# master.net
KiCad netlist of a schematic drawn in Altium Designer
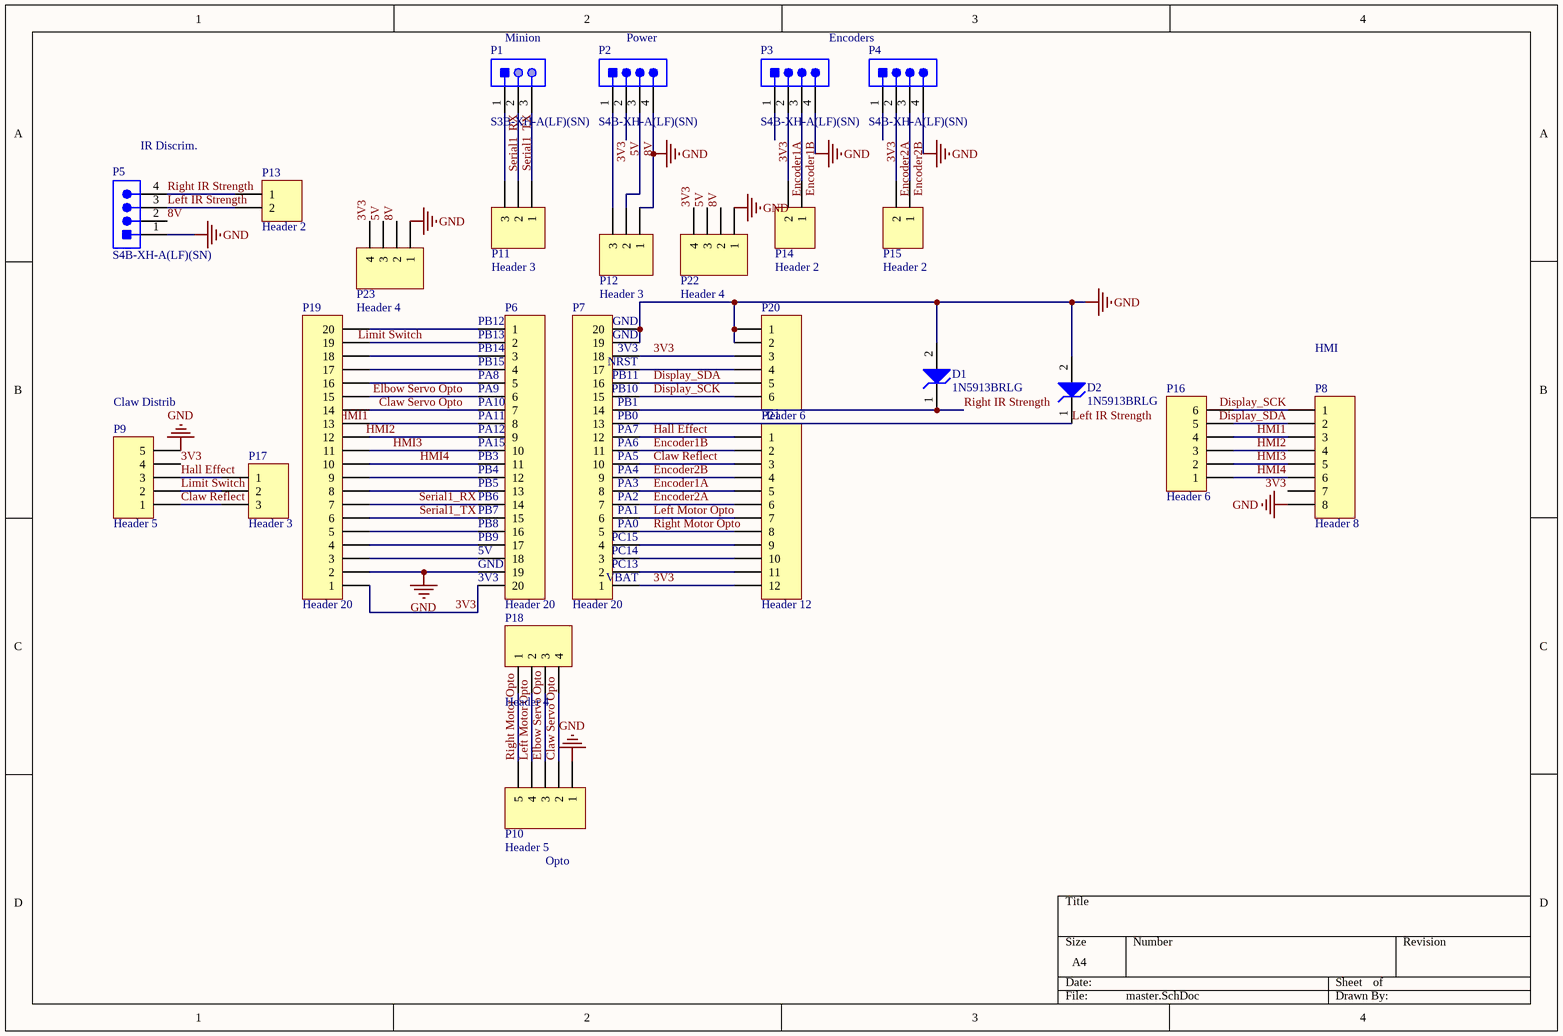
[diagram p0: master.SchDoc]

(export (version "E")
  (design (tool "Eeschema 10.0.6"))
  (components
    (comp (ref "D1")
      (value "1N5913BRLG")
      (footprint "ONSC-AXIAL_LEAD-2-59-10_P")
      (description "3 W Zener Voltage Regulator, 2-Pin Axial_Lead, Pb-Free, Tape and Reel")
      (fields (field (name "MANUFACTURER") "On Semiconductor"))
      (libsource (lib "Altium Content Vault") (part "ONSC-K1A2-2"))
    )
    (comp (ref "D2")
      (value "1N5913BRLG")
      (footprint "ONSC-AXIAL_LEAD-2-59-10_P")
      (description "3 W Zener Voltage Regulator, 2-Pin Axial_Lead, Pb-Free, Tape and Reel")
      (fields (field (name "MANUFACTURER") "On Semiconductor"))
      (libsource (lib "Altium Content Vault") (part "ONSC-K1A2-2"))
    )
    (comp (ref "P1")
      (value "S3B-XH-A(LF)(SN)")
      (footprint "JST-S3B-XH-A(LF)(SN)_V")
      (libsource (lib "Altium Content Vault") (part "CN-1P-M-R3"))
    )
    (comp (ref "P2")
      (value "S4B-XH-A(LF)(SN)")
      (footprint "JST-S4B-XH-A(LF)(SN)_V")
      (libsource (lib "") (part "CN-1P-M-R4_1"))
    )
    (comp (ref "P3")
      (value "S4B-XH-A(LF)(SN)")
      (footprint "JST-S4B-XH-A(LF)(SN)_V")
      (libsource (lib "") (part "CN-1P-M-R4_1"))
    )
    (comp (ref "P4")
      (value "S4B-XH-A(LF)(SN)")
      (footprint "JST-S4B-XH-A(LF)(SN)_V")
      (libsource (lib "") (part "CN-1P-M-R4_1"))
    )
    (comp (ref "P5")
      (value "S4B-XH-A(LF)(SN)")
      (footprint "JST-S4B-XH-A(LF)(SN)_V")
      (libsource (lib "Altium Content Vault") (part "CN-1P-M-R4"))
    )
    (comp (ref "P6")
      (value "Header 20")
      (footprint "HDR1X20")
      (description "Header, 20-Pin")
      (fields (field (name "PUBLISHER") "Altium Limited"))
      (libsource (lib "") (part "Header 20_1"))
    )
    (comp (ref "P7")
      (value "Header 20")
      (footprint "HDR1X20")
      (description "Header, 20-Pin")
      (fields (field (name "PUBLISHER") "Altium Limited"))
      (libsource (lib "Miscellaneous Connectors") (part "Header 20"))
    )
    (comp (ref "P8")
      (value "Header 8")
      (footprint "HDR1X8")
      (description "Header, 8-Pin")
      (fields (field (name "PUBLISHER") "Altium Limited"))
      (libsource (lib "Miscellaneous Connectors") (part "Header 8"))
    )
    (comp (ref "P9")
      (value "Header 5")
      (footprint "HDR1X5")
      (description "Header, 5-Pin")
      (fields (field (name "PUBLISHER") "Altium Limited"))
      (libsource (lib "Miscellaneous Connectors") (part "Header 5"))
    )
    (comp (ref "P10")
      (value "Header 5")
      (footprint "HDR1X5")
      (description "Header, 5-Pin")
      (fields (field (name "PUBLISHER") "Altium Limited"))
      (libsource (lib "") (part "Header 5_1"))
    )
    (comp (ref "P11")
      (value "Header 3")
      (footprint "HDR1X3")
      (description "Header, 3-Pin")
      (fields (field (name "PUBLISHER") "Altium Limited"))
      (libsource (lib "Miscellaneous Connectors") (part "Header 3"))
    )
    (comp (ref "P12")
      (value "Header 3")
      (footprint "HDR1X3")
      (description "Header, 3-Pin")
      (fields (field (name "PUBLISHER") "Altium Limited"))
      (libsource (lib "Miscellaneous Connectors") (part "Header 3"))
    )
    (comp (ref "P13")
      (value "Header 2")
      (footprint "HDR1X2")
      (description "Header, 2-Pin")
      (fields (field (name "PUBLISHER") "Altium Limited"))
      (libsource (lib "") (part "Header 2_1"))
    )
    (comp (ref "P14")
      (value "Header 2")
      (footprint "HDR1X2")
      (description "Header, 2-Pin")
      (fields (field (name "PUBLISHER") "Altium Limited"))
      (libsource (lib "Miscellaneous Connectors") (part "Header 2"))
    )
    (comp (ref "P15")
      (value "Header 2")
      (footprint "HDR1X2")
      (description "Header, 2-Pin")
      (fields (field (name "PUBLISHER") "Altium Limited"))
      (libsource (lib "Miscellaneous Connectors") (part "Header 2"))
    )
    (comp (ref "P16")
      (value "Header 6")
      (footprint "HDR1X6")
      (description "Header, 6-Pin")
      (fields (field (name "PUBLISHER") "Altium Limited"))
      (libsource (lib "") (part "Header 6_1"))
    )
    (comp (ref "P17")
      (value "Header 3")
      (footprint "HDR1X3")
      (description "Header, 3-Pin")
      (fields (field (name "PUBLISHER") "Altium Limited"))
      (libsource (lib "") (part "Header 3_1"))
    )
    (comp (ref "P18")
      (value "Header 4")
      (footprint "HDR1X4")
      (description "Header, 4-Pin")
      (fields (field (name "PUBLISHER") "Altium Limited"))
      (libsource (lib "Miscellaneous Connectors") (part "Header 4"))
    )
    (comp (ref "P19")
      (value "Header 20")
      (footprint "HDR1X20")
      (description "Header, 20-Pin")
      (fields (field (name "PUBLISHER") "Altium Limited"))
      (libsource (lib "Miscellaneous Connectors") (part "Header 20"))
    )
    (comp (ref "P20")
      (value "Header 6")
      (footprint "HDR1X6")
      (description "Header, 6-Pin")
      (fields (field (name "PUBLISHER") "Altium Limited"))
      (libsource (lib "Miscellaneous Connectors") (part "Header 6"))
    )
    (comp (ref "P21")
      (value "Header 12")
      (footprint "HDR1X12")
      (description "Header, 12-Pin")
      (fields (field (name "PUBLISHER") "Altium Limited"))
      (libsource (lib "Miscellaneous Connectors") (part "Header 12"))
    )
    (comp (ref "P22")
      (value "Header 4")
      (footprint "HDR1X4")
      (description "Header, 4-Pin")
      (fields (field (name "PUBLISHER") "Altium Limited"))
      (libsource (lib "") (part "Header 4_1"))
    )
    (comp (ref "P23")
      (value "Header 4")
      (footprint "HDR1X4")
      (description "Header, 4-Pin")
      (fields (field (name "PUBLISHER") "Altium Limited"))
      (libsource (lib "") (part "Header 4_1"))
    )
  )
  (nets
    (net (code "1") (name "/3V3") (class "Default")
      (node (ref "P12") (pin "3") (pinfunction "3_3") (pintype "passive"))
      (node (ref "P19") (pin "1") (pinfunction "1_1") (pintype "passive"))
      (node (ref "P2") (pin "1") (pinfunction "1_1") (pintype "passive"))
      (node (ref "P20") (pin "3") (pinfunction "3_3") (pintype "passive"))
      (node (ref "P21") (pin "12") (pinfunction "12_12") (pintype "passive"))
      (node (ref "P22") (pin "4") (pinfunction "4_4") (pintype "passive"))
      (node (ref "P23") (pin "4") (pinfunction "4_4") (pintype "passive"))
      (node (ref "P3") (pin "1") (pinfunction "1_1") (pintype "passive"))
      (node (ref "P4") (pin "1") (pinfunction "1_1") (pintype "passive"))
      (node (ref "P6") (pin "20") (pinfunction "20_20") (pintype "passive"))
      (node (ref "P7") (pin "1") (pinfunction "1_1") (pintype "passive"))
      (node (ref "P7") (pin "18") (pinfunction "18_18") (pintype "passive"))
      (node (ref "P8") (pin "7") (pinfunction "7_7") (pintype "passive"))
      (node (ref "P9") (pin "4") (pinfunction "4_4") (pintype "passive"))
    )
    (net (code "2") (name "/5V") (class "Default")
      (node (ref "P2") (pin "2") (pinfunction "2_2") (pintype "passive"))
      (node (ref "P22") (pin "3") (pinfunction "3_3") (pintype "passive"))
      (node (ref "P23") (pin "3") (pinfunction "3_3") (pintype "passive"))
    )
    (net (code "3") (name "/8V") (class "Default")
      (node (ref "P12") (pin "2") (pinfunction "2_2") (pintype "passive"))
      (node (ref "P2") (pin "3") (pinfunction "3_3") (pintype "passive"))
      (node (ref "P22") (pin "2") (pinfunction "2_2") (pintype "passive"))
      (node (ref "P23") (pin "2") (pinfunction "2_2") (pintype "passive"))
      (node (ref "P5") (pin "2") (pinfunction "2_2") (pintype "passive"))
    )
    (net (code "4") (name "/Claw Reflect") (class "Default")
      (node (ref "P17") (pin "3") (pinfunction "3_3") (pintype "passive"))
      (node (ref "P21") (pin "3") (pinfunction "3_3") (pintype "passive"))
      (node (ref "P7") (pin "10") (pinfunction "10_10") (pintype "passive"))
      (node (ref "P9") (pin "1") (pinfunction "1_1") (pintype "passive"))
    )
    (net (code "5") (name "/Claw Servo Opto") (class "Default")
      (node (ref "P10") (pin "2") (pinfunction "2_2") (pintype "passive"))
      (node (ref "P18") (pin "4") (pinfunction "4_4") (pintype "passive"))
      (node (ref "P19") (pin "14") (pinfunction "14_14") (pintype "passive"))
      (node (ref "P6") (pin "7") (pinfunction "7_7") (pintype "passive"))
    )
    (net (code "6") (name "/Display_SCK") (class "Default")
      (node (ref "P16") (pin "6") (pinfunction "6_6") (pintype "passive"))
      (node (ref "P20") (pin "6") (pinfunction "6_6") (pintype "passive"))
      (node (ref "P7") (pin "15") (pinfunction "15_15") (pintype "passive"))
      (node (ref "P8") (pin "1") (pinfunction "1_1") (pintype "passive"))
    )
    (net (code "7") (name "/Display_SDA") (class "Default")
      (node (ref "P16") (pin "5") (pinfunction "5_5") (pintype "passive"))
      (node (ref "P20") (pin "5") (pinfunction "5_5") (pintype "passive"))
      (node (ref "P7") (pin "16") (pinfunction "16_16") (pintype "passive"))
      (node (ref "P8") (pin "2") (pinfunction "2_2") (pintype "passive"))
    )
    (net (code "8") (name "/Elbow Servo Opto") (class "Default")
      (node (ref "P10") (pin "3") (pinfunction "3_3") (pintype "passive"))
      (node (ref "P18") (pin "3") (pinfunction "3_3") (pintype "passive"))
      (node (ref "P19") (pin "15") (pinfunction "15_15") (pintype "passive"))
      (node (ref "P6") (pin "6") (pinfunction "6_6") (pintype "passive"))
    )
    (net (code "9") (name "/Encoder1A") (class "Default")
      (node (ref "P14") (pin "2") (pinfunction "2_2") (pintype "passive"))
      (node (ref "P21") (pin "5") (pinfunction "5_5") (pintype "passive"))
      (node (ref "P3") (pin "2") (pinfunction "2_2") (pintype "passive"))
      (node (ref "P7") (pin "8") (pinfunction "8_8") (pintype "passive"))
    )
    (net (code "10") (name "/Encoder1B") (class "Default")
      (node (ref "P14") (pin "1") (pinfunction "1_1") (pintype "passive"))
      (node (ref "P21") (pin "2") (pinfunction "2_2") (pintype "passive"))
      (node (ref "P3") (pin "3") (pinfunction "3_3") (pintype "passive"))
      (node (ref "P7") (pin "11") (pinfunction "11_11") (pintype "passive"))
    )
    (net (code "11") (name "/Encoder2A") (class "Default")
      (node (ref "P15") (pin "2") (pinfunction "2_2") (pintype "passive"))
      (node (ref "P21") (pin "6") (pinfunction "6_6") (pintype "passive"))
      (node (ref "P4") (pin "2") (pinfunction "2_2") (pintype "passive"))
      (node (ref "P7") (pin "7") (pinfunction "7_7") (pintype "passive"))
    )
    (net (code "12") (name "/Encoder2B") (class "Default")
      (node (ref "P15") (pin "1") (pinfunction "1_1") (pintype "passive"))
      (node (ref "P21") (pin "4") (pinfunction "4_4") (pintype "passive"))
      (node (ref "P4") (pin "3") (pinfunction "3_3") (pintype "passive"))
      (node (ref "P7") (pin "9") (pinfunction "9_9") (pintype "passive"))
    )
    (net (code "13") (name "/HMI1") (class "Default")
      (node (ref "P16") (pin "4") (pinfunction "4_4") (pintype "passive"))
      (node (ref "P19") (pin "13") (pinfunction "13_13") (pintype "passive"))
      (node (ref "P6") (pin "8") (pinfunction "8_8") (pintype "passive"))
      (node (ref "P8") (pin "3") (pinfunction "3_3") (pintype "passive"))
    )
    (net (code "14") (name "/HMI2") (class "Default")
      (node (ref "P16") (pin "3") (pinfunction "3_3") (pintype "passive"))
      (node (ref "P19") (pin "12") (pinfunction "12_12") (pintype "passive"))
      (node (ref "P6") (pin "9") (pinfunction "9_9") (pintype "passive"))
      (node (ref "P8") (pin "4") (pinfunction "4_4") (pintype "passive"))
    )
    (net (code "15") (name "/HMI3") (class "Default")
      (node (ref "P16") (pin "2") (pinfunction "2_2") (pintype "passive"))
      (node (ref "P19") (pin "11") (pinfunction "11_11") (pintype "passive"))
      (node (ref "P6") (pin "10") (pinfunction "10_10") (pintype "passive"))
      (node (ref "P8") (pin "5") (pinfunction "5_5") (pintype "passive"))
    )
    (net (code "16") (name "/HMI4") (class "Default")
      (node (ref "P16") (pin "1") (pinfunction "1_1") (pintype "passive"))
      (node (ref "P19") (pin "10") (pinfunction "10_10") (pintype "passive"))
      (node (ref "P6") (pin "11") (pinfunction "11_11") (pintype "passive"))
      (node (ref "P8") (pin "6") (pinfunction "6_6") (pintype "passive"))
    )
    (net (code "17") (name "/Hall Effect") (class "Default")
      (node (ref "P17") (pin "1") (pinfunction "1_1") (pintype "passive"))
      (node (ref "P21") (pin "1") (pinfunction "1_1") (pintype "passive"))
      (node (ref "P7") (pin "12") (pinfunction "12_12") (pintype "passive"))
      (node (ref "P9") (pin "3") (pinfunction "3_3") (pintype "passive"))
    )
    (net (code "18") (name "/Left IR Strength") (class "Default")
      (node (ref "D2") (pin "1") (pinfunction "K_1") (pintype "passive"))
      (node (ref "P13") (pin "2") (pinfunction "2_2") (pintype "passive"))
      (node (ref "P5") (pin "3") (pinfunction "3_3") (pintype "passive"))
      (node (ref "P7") (pin "13") (pinfunction "13_13") (pintype "passive"))
    )
    (net (code "19") (name "/Left Motor Opto") (class "Default")
      (node (ref "P10") (pin "4") (pinfunction "4_4") (pintype "passive"))
      (node (ref "P18") (pin "2") (pinfunction "2_2") (pintype "passive"))
      (node (ref "P21") (pin "7") (pinfunction "7_7") (pintype "passive"))
      (node (ref "P7") (pin "6") (pinfunction "6_6") (pintype "passive"))
    )
    (net (code "20") (name "/Limit Switch") (class "Default")
      (node (ref "P17") (pin "2") (pinfunction "2_2") (pintype "passive"))
      (node (ref "P19") (pin "19") (pinfunction "19_19") (pintype "passive"))
      (node (ref "P6") (pin "2") (pinfunction "2_2") (pintype "passive"))
      (node (ref "P9") (pin "2") (pinfunction "2_2") (pintype "passive"))
    )
    (net (code "21") (name "/Right IR Strength") (class "Default")
      (node (ref "D1") (pin "1") (pinfunction "K_1") (pintype "passive"))
      (node (ref "P13") (pin "1") (pinfunction "1_1") (pintype "passive"))
      (node (ref "P5") (pin "4") (pinfunction "4_4") (pintype "passive"))
      (node (ref "P7") (pin "14") (pinfunction "14_14") (pintype "passive"))
    )
    (net (code "22") (name "/Right Motor Opto") (class "Default")
      (node (ref "P10") (pin "5") (pinfunction "5_5") (pintype "passive"))
      (node (ref "P18") (pin "1") (pinfunction "1_1") (pintype "passive"))
      (node (ref "P21") (pin "8") (pinfunction "8_8") (pintype "passive"))
      (node (ref "P7") (pin "5") (pinfunction "5_5") (pintype "passive"))
    )
    (net (code "23") (name "/Serial1_RX") (class "Default")
      (node (ref "P1") (pin "1") (pinfunction "1_1") (pintype "passive"))
      (node (ref "P11") (pin "3") (pinfunction "3_3") (pintype "passive"))
      (node (ref "P19") (pin "7") (pinfunction "7_7") (pintype "passive"))
      (node (ref "P6") (pin "14") (pinfunction "14_14") (pintype "passive"))
    )
    (net (code "24") (name "/Serial1_TX") (class "Default")
      (node (ref "P1") (pin "2") (pinfunction "2_2") (pintype "passive"))
      (node (ref "P11") (pin "2") (pinfunction "2_2") (pintype "passive"))
      (node (ref "P19") (pin "6") (pinfunction "6_6") (pintype "passive"))
      (node (ref "P6") (pin "15") (pinfunction "15_15") (pintype "passive"))
    )
    (net (code "25") (name "GND") (class "Default")
      (node (ref "D1") (pin "2") (pinfunction "A_2") (pintype "passive"))
      (node (ref "D2") (pin "2") (pinfunction "A_2") (pintype "passive"))
      (node (ref "P10") (pin "1") (pinfunction "1_1") (pintype "passive"))
      (node (ref "P12") (pin "1") (pinfunction "1_1") (pintype "passive"))
      (node (ref "P19") (pin "2") (pinfunction "2_2") (pintype "passive"))
      (node (ref "P2") (pin "4") (pinfunction "4_4") (pintype "passive"))
      (node (ref "P20") (pin "1") (pinfunction "1_1") (pintype "passive"))
      (node (ref "P20") (pin "2") (pinfunction "2_2") (pintype "passive"))
      (node (ref "P22") (pin "1") (pinfunction "1_1") (pintype "passive"))
      (node (ref "P23") (pin "1") (pinfunction "1_1") (pintype "passive"))
      (node (ref "P3") (pin "4") (pinfunction "4_4") (pintype "passive"))
      (node (ref "P4") (pin "4") (pinfunction "4_4") (pintype "passive"))
      (node (ref "P5") (pin "1") (pinfunction "1_1") (pintype "passive"))
      (node (ref "P6") (pin "19") (pinfunction "19_19") (pintype "passive"))
      (node (ref "P7") (pin "19") (pinfunction "19_19") (pintype "passive"))
      (node (ref "P7") (pin "20") (pinfunction "20_20") (pintype "passive"))
      (node (ref "P8") (pin "8") (pinfunction "8_8") (pintype "passive"))
      (node (ref "P9") (pin "5") (pinfunction "5_5") (pintype "passive"))
    )
    (net (code "26") (name "Net-(P1-Pad3)") (class "Default")
      (node (ref "P1") (pin "3") (pinfunction "3_3") (pintype "passive"))
      (node (ref "P11") (pin "1") (pinfunction "1_1") (pintype "passive"))
    )
    (net (code "27") (name "Net-(P19-Pad3)") (class "Default")
      (node (ref "P19") (pin "3") (pinfunction "3_3") (pintype "passive"))
      (node (ref "P6") (pin "18") (pinfunction "18_18") (pintype "passive"))
    )
    (net (code "28") (name "Net-(P19-Pad4)") (class "Default")
      (node (ref "P19") (pin "4") (pinfunction "4_4") (pintype "passive"))
      (node (ref "P6") (pin "17") (pinfunction "17_17") (pintype "passive"))
    )
    (net (code "29") (name "Net-(P19-Pad5)") (class "Default")
      (node (ref "P19") (pin "5") (pinfunction "5_5") (pintype "passive"))
      (node (ref "P6") (pin "16") (pinfunction "16_16") (pintype "passive"))
    )
    (net (code "30") (name "Net-(P19-Pad8)") (class "Default")
      (node (ref "P19") (pin "8") (pinfunction "8_8") (pintype "passive"))
      (node (ref "P6") (pin "13") (pinfunction "13_13") (pintype "passive"))
    )
    (net (code "31") (name "Net-(P19-Pad9)") (class "Default")
      (node (ref "P19") (pin "9") (pinfunction "9_9") (pintype "passive"))
      (node (ref "P6") (pin "12") (pinfunction "12_12") (pintype "passive"))
    )
    (net (code "32") (name "Net-(P19-Pad16)") (class "Default")
      (node (ref "P19") (pin "16") (pinfunction "16_16") (pintype "passive"))
      (node (ref "P6") (pin "5") (pinfunction "5_5") (pintype "passive"))
    )
    (net (code "33") (name "Net-(P19-Pad17)") (class "Default")
      (node (ref "P19") (pin "17") (pinfunction "17_17") (pintype "passive"))
      (node (ref "P6") (pin "4") (pinfunction "4_4") (pintype "passive"))
    )
    (net (code "34") (name "Net-(P19-Pad18)") (class "Default")
      (node (ref "P19") (pin "18") (pinfunction "18_18") (pintype "passive"))
      (node (ref "P6") (pin "3") (pinfunction "3_3") (pintype "passive"))
    )
    (net (code "35") (name "Net-(P19-Pad20)") (class "Default")
      (node (ref "P19") (pin "20") (pinfunction "20_20") (pintype "passive"))
      (node (ref "P6") (pin "1") (pinfunction "1_1") (pintype "passive"))
    )
    (net (code "36") (name "Net-(P20-Pad4)") (class "Default")
      (node (ref "P20") (pin "4") (pinfunction "4_4") (pintype "passive"))
      (node (ref "P7") (pin "17") (pinfunction "17_17") (pintype "passive"))
    )
    (net (code "37") (name "Net-(P21-Pad9)") (class "Default")
      (node (ref "P21") (pin "9") (pinfunction "9_9") (pintype "passive"))
      (node (ref "P7") (pin "4") (pinfunction "4_4") (pintype "passive"))
    )
    (net (code "38") (name "Net-(P21-Pad10)") (class "Default")
      (node (ref "P21") (pin "10") (pinfunction "10_10") (pintype "passive"))
      (node (ref "P7") (pin "3") (pinfunction "3_3") (pintype "passive"))
    )
    (net (code "39") (name "Net-(P21-Pad11)") (class "Default")
      (node (ref "P21") (pin "11") (pinfunction "11_11") (pintype "passive"))
      (node (ref "P7") (pin "2") (pinfunction "2_2") (pintype "passive"))
    )
  )
)
